# BD0005_1_main.net
KiCad netlist of a schematic drawn in EAGLE
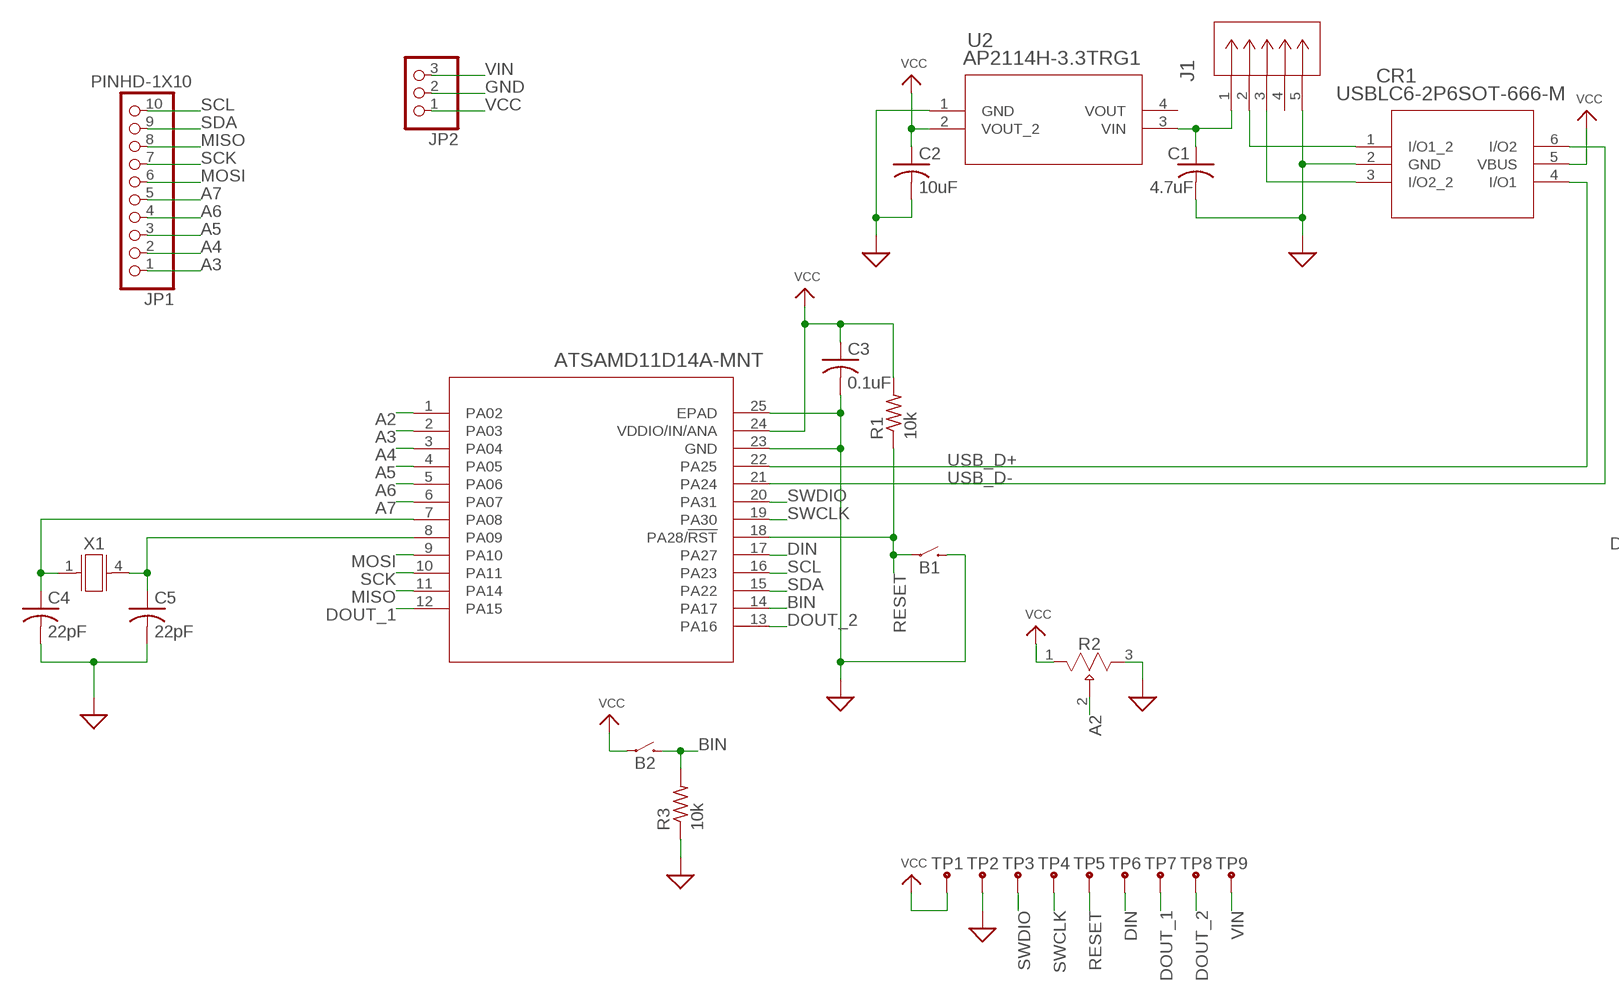
[diagram p0: schematic, sheet 1, part 1 of 2]
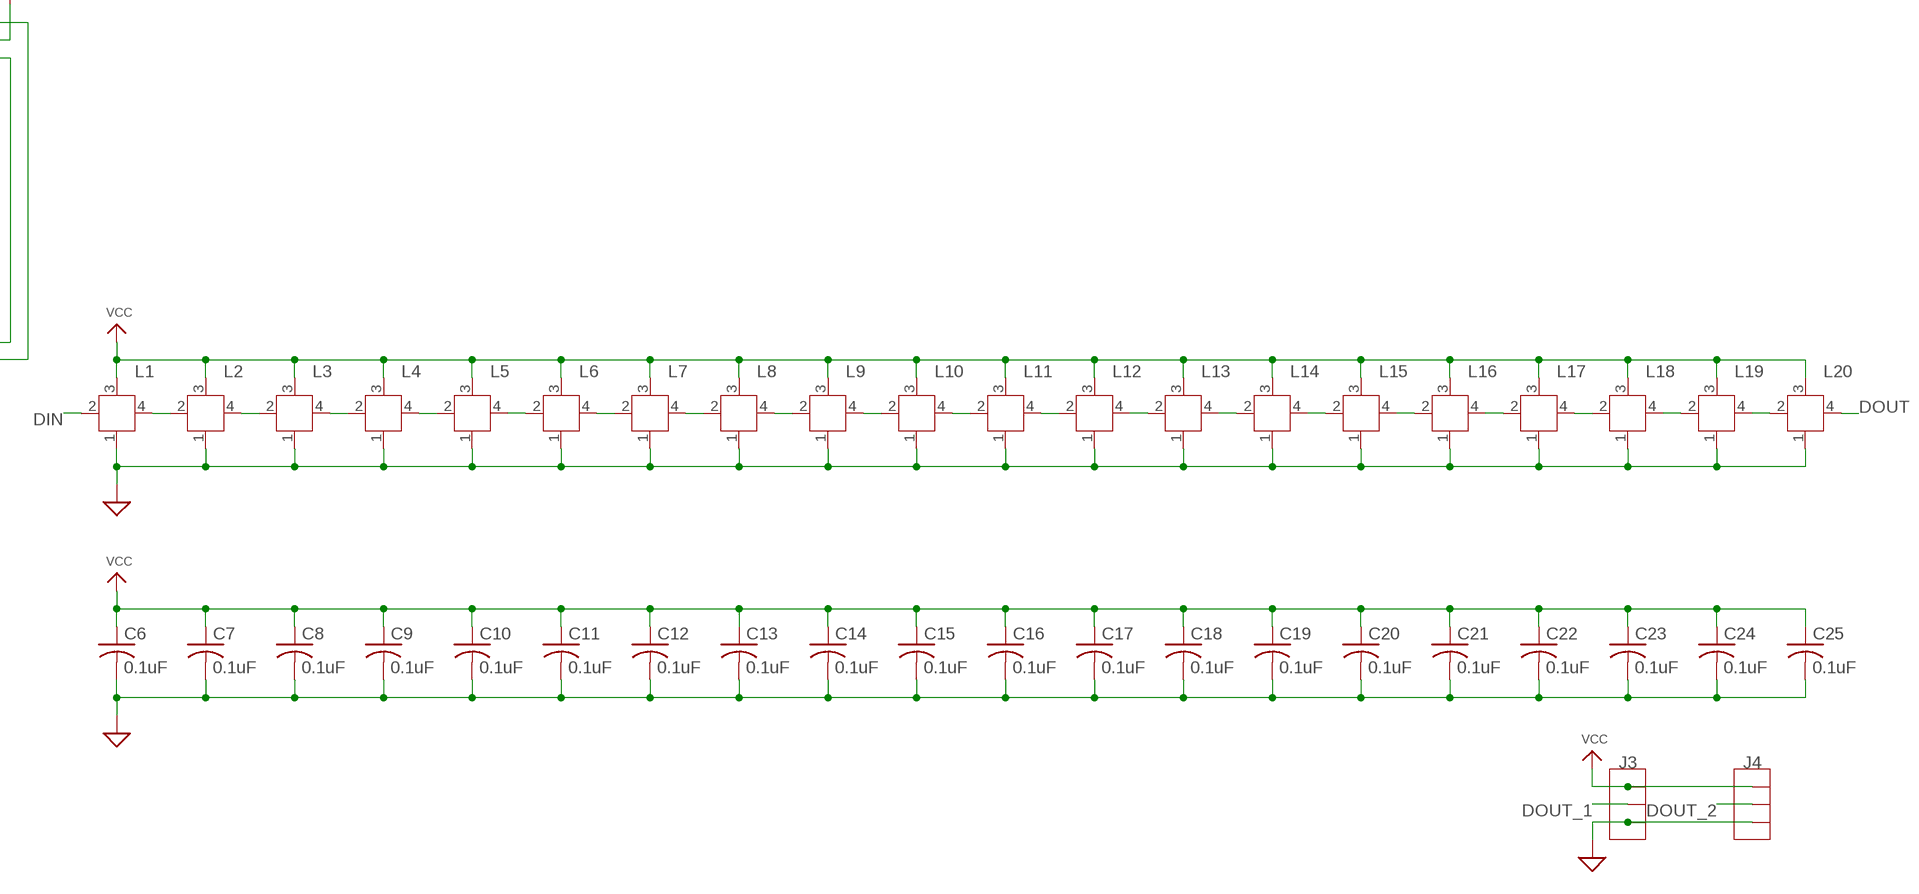
[diagram p1: schematic, sheet 1, part 2 of 2]

(export (version "E")
  (design (tool "Eeschema 10.0.6"))
  (components
    (comp (ref "B1")
      (value "EVQ-P7A01P")
      (footprint "eagle-import:4-SMD_BUTTON")
      (libsource (lib "eagle-import") (part "EVQ-P7A01P"))
    )
    (comp (ref "B2")
      (value "EVQ-P7A01P")
      (footprint "eagle-import:4-SMD_BUTTON")
      (libsource (lib "eagle-import") (part "EVQ-P7A01P"))
    )
    (comp (ref "C1")
      (value "4.7uF")
      (footprint "eagle-import:C0805")
      (libsource (lib "eagle-import") (part "C-USC0805"))
    )
    (comp (ref "C2")
      (value "10uF")
      (footprint "eagle-import:C0805")
      (libsource (lib "eagle-import") (part "C-USC0805"))
    )
    (comp (ref "C3")
      (value "0.1uF")
      (footprint "eagle-import:C0402")
      (libsource (lib "eagle-import") (part "C-USC0402"))
    )
    (comp (ref "C4")
      (value "22pF")
      (footprint "eagle-import:C0402")
      (libsource (lib "eagle-import") (part "C-USC0402"))
    )
    (comp (ref "C5")
      (value "22pF")
      (footprint "eagle-import:C0402")
      (libsource (lib "eagle-import") (part "C-USC0402"))
    )
    (comp (ref "C6")
      (value "0.1uF")
      (footprint "eagle-import:C0402")
      (libsource (lib "eagle-import") (part "C-USC0402"))
    )
    (comp (ref "C7")
      (value "0.1uF")
      (footprint "eagle-import:C0402")
      (libsource (lib "eagle-import") (part "C-USC0402"))
    )
    (comp (ref "C8")
      (value "0.1uF")
      (footprint "eagle-import:C0402")
      (libsource (lib "eagle-import") (part "C-USC0402"))
    )
    (comp (ref "C9")
      (value "0.1uF")
      (footprint "eagle-import:C0402")
      (libsource (lib "eagle-import") (part "C-USC0402"))
    )
    (comp (ref "C10")
      (value "0.1uF")
      (footprint "eagle-import:C0402")
      (libsource (lib "eagle-import") (part "C-USC0402"))
    )
    (comp (ref "C11")
      (value "0.1uF")
      (footprint "eagle-import:C0402")
      (libsource (lib "eagle-import") (part "C-USC0402"))
    )
    (comp (ref "C12")
      (value "0.1uF")
      (footprint "eagle-import:C0402")
      (libsource (lib "eagle-import") (part "C-USC0402"))
    )
    (comp (ref "C13")
      (value "0.1uF")
      (footprint "eagle-import:C0402")
      (libsource (lib "eagle-import") (part "C-USC0402"))
    )
    (comp (ref "C14")
      (value "0.1uF")
      (footprint "eagle-import:C0402")
      (libsource (lib "eagle-import") (part "C-USC0402"))
    )
    (comp (ref "C15")
      (value "0.1uF")
      (footprint "eagle-import:C0402")
      (libsource (lib "eagle-import") (part "C-USC0402"))
    )
    (comp (ref "C16")
      (value "0.1uF")
      (footprint "eagle-import:C0402")
      (libsource (lib "eagle-import") (part "C-USC0402"))
    )
    (comp (ref "C17")
      (value "0.1uF")
      (footprint "eagle-import:C0402")
      (libsource (lib "eagle-import") (part "C-USC0402"))
    )
    (comp (ref "C18")
      (value "0.1uF")
      (footprint "eagle-import:C0402")
      (libsource (lib "eagle-import") (part "C-USC0402"))
    )
    (comp (ref "C19")
      (value "0.1uF")
      (footprint "eagle-import:C0402")
      (libsource (lib "eagle-import") (part "C-USC0402"))
    )
    (comp (ref "C20")
      (value "0.1uF")
      (footprint "eagle-import:C0402")
      (libsource (lib "eagle-import") (part "C-USC0402"))
    )
    (comp (ref "C21")
      (value "0.1uF")
      (footprint "eagle-import:C0402")
      (libsource (lib "eagle-import") (part "C-USC0402"))
    )
    (comp (ref "C22")
      (value "0.1uF")
      (footprint "eagle-import:C0402")
      (libsource (lib "eagle-import") (part "C-USC0402"))
    )
    (comp (ref "C23")
      (value "0.1uF")
      (footprint "eagle-import:C0402")
      (libsource (lib "eagle-import") (part "C-USC0402"))
    )
    (comp (ref "C24")
      (value "0.1uF")
      (footprint "eagle-import:C0402")
      (libsource (lib "eagle-import") (part "C-USC0402"))
    )
    (comp (ref "C25")
      (value "0.1uF")
      (footprint "eagle-import:C0402")
      (libsource (lib "eagle-import") (part "C-USC0402"))
    )
    (comp (ref "CR1")
      (value "USBLC6-2P6SOT-666-M")
      (footprint "eagle-import:SOT-666-M")
      (fields (field (name "MANUFACTURER_PART_NUMBER") "USBLC6-2P6"))
      (libsource (lib "eagle-import") (part "USBLC6-2P6SOT-666-M"))
    )
    (comp (ref "J1")
      (value "1050171001")
      (footprint "eagle-import:CON00679_5")
      (fields (field (name "COPYRIGHT") "Copyright (C) 2016 Accelerated Designs. All rights reserved"))
      (libsource (lib "eagle-import") (part "1050171001"))
    )
    (comp (ref "J3")
      (value "HEADER_1X3FEMALE")
      (footprint "eagle-import:F3SMD")
      (libsource (lib "eagle-import") (part "HEADER_1X3FEMALE"))
    )
    (comp (ref "J4")
      (value "HEADER_1X3FEMALE")
      (footprint "eagle-import:F3SMD")
      (libsource (lib "eagle-import") (part "HEADER_1X3FEMALE"))
    )
    (comp (ref "JP1")
      (value "PINHD-1X10")
      (footprint "eagle-import:1X10-BIG")
      (libsource (lib "eagle-import") (part "PINHD-1X10"))
    )
    (comp (ref "JP2")
      (value "PINHD-1X3")
      (footprint "eagle-import:1X03")
      (libsource (lib "eagle-import") (part "PINHD-1X3"))
    )
    (comp (ref "L1")
      (value "WS2812B")
      (footprint "eagle-import:SK6812")
      (libsource (lib "eagle-import") (part "WS2812B"))
    )
    (comp (ref "L2")
      (value "WS2812B")
      (footprint "eagle-import:SK6812")
      (libsource (lib "eagle-import") (part "WS2812B"))
    )
    (comp (ref "L3")
      (value "WS2812B")
      (footprint "eagle-import:SK6812")
      (libsource (lib "eagle-import") (part "WS2812B"))
    )
    (comp (ref "L4")
      (value "WS2812B")
      (footprint "eagle-import:SK6812")
      (libsource (lib "eagle-import") (part "WS2812B"))
    )
    (comp (ref "L5")
      (value "WS2812B")
      (footprint "eagle-import:SK6812")
      (libsource (lib "eagle-import") (part "WS2812B"))
    )
    (comp (ref "L6")
      (value "WS2812B")
      (footprint "eagle-import:SK6812")
      (libsource (lib "eagle-import") (part "WS2812B"))
    )
    (comp (ref "L7")
      (value "WS2812B")
      (footprint "eagle-import:SK6812")
      (libsource (lib "eagle-import") (part "WS2812B"))
    )
    (comp (ref "L8")
      (value "WS2812B")
      (footprint "eagle-import:SK6812")
      (libsource (lib "eagle-import") (part "WS2812B"))
    )
    (comp (ref "L9")
      (value "WS2812B")
      (footprint "eagle-import:SK6812")
      (libsource (lib "eagle-import") (part "WS2812B"))
    )
    (comp (ref "L10")
      (value "WS2812B")
      (footprint "eagle-import:SK6812")
      (libsource (lib "eagle-import") (part "WS2812B"))
    )
    (comp (ref "L11")
      (value "WS2812B")
      (footprint "eagle-import:SK6812")
      (libsource (lib "eagle-import") (part "WS2812B"))
    )
    (comp (ref "L12")
      (value "WS2812B")
      (footprint "eagle-import:SK6812")
      (libsource (lib "eagle-import") (part "WS2812B"))
    )
    (comp (ref "L13")
      (value "WS2812B")
      (footprint "eagle-import:SK6812")
      (libsource (lib "eagle-import") (part "WS2812B"))
    )
    (comp (ref "L14")
      (value "WS2812B")
      (footprint "eagle-import:SK6812")
      (libsource (lib "eagle-import") (part "WS2812B"))
    )
    (comp (ref "L15")
      (value "WS2812B")
      (footprint "eagle-import:SK6812")
      (libsource (lib "eagle-import") (part "WS2812B"))
    )
    (comp (ref "L16")
      (value "WS2812B")
      (footprint "eagle-import:SK6812")
      (libsource (lib "eagle-import") (part "WS2812B"))
    )
    (comp (ref "L17")
      (value "WS2812B")
      (footprint "eagle-import:SK6812")
      (libsource (lib "eagle-import") (part "WS2812B"))
    )
    (comp (ref "L18")
      (value "WS2812B")
      (footprint "eagle-import:SK6812")
      (libsource (lib "eagle-import") (part "WS2812B"))
    )
    (comp (ref "L19")
      (value "WS2812B")
      (footprint "eagle-import:SK6812")
      (libsource (lib "eagle-import") (part "WS2812B"))
    )
    (comp (ref "L20")
      (value "WS2812B")
      (footprint "eagle-import:SK6812")
      (libsource (lib "eagle-import") (part "WS2812B"))
    )
    (comp (ref "R1")
      (value "10k")
      (footprint "eagle-import:R0402")
      (libsource (lib "eagle-import") (part "R-US_R0402"))
    )
    (comp (ref "R2")
      (value "3352T-1-104LF")
      (footprint "eagle-import:THUMBWHEEL")
      (libsource (lib "eagle-import") (part "3352T-1-104LF"))
    )
    (comp (ref "R3")
      (value "10k")
      (footprint "eagle-import:R0402")
      (libsource (lib "eagle-import") (part "R-US_R0402"))
    )
    (comp (ref "TP1")
      (value "VCC")
      (footprint "eagle-import:TEST_POINT")
      (libsource (lib "eagle-import") (part "TEST_POINT"))
    )
    (comp (ref "TP2")
      (value "GND")
      (footprint "eagle-import:TEST_POINT")
      (libsource (lib "eagle-import") (part "TEST_POINT"))
    )
    (comp (ref "TP3")
      (value "DIO")
      (footprint "eagle-import:TEST_POINT")
      (libsource (lib "eagle-import") (part "TEST_POINT"))
    )
    (comp (ref "TP4")
      (value "CLK")
      (footprint "eagle-import:TEST_POINT")
      (libsource (lib "eagle-import") (part "TEST_POINT"))
    )
    (comp (ref "TP5")
      (value "RST")
      (footprint "eagle-import:TEST_POINT")
      (libsource (lib "eagle-import") (part "TEST_POINT"))
    )
    (comp (ref "TP6")
      (value "DIN")
      (footprint "eagle-import:TEST_POINT")
      (libsource (lib "eagle-import") (part "TEST_POINT"))
    )
    (comp (ref "TP7")
      (value "DO1")
      (footprint "eagle-import:TEST_POINT")
      (libsource (lib "eagle-import") (part "TEST_POINT"))
    )
    (comp (ref "TP8")
      (value "DO2")
      (footprint "eagle-import:TEST_POINT")
      (libsource (lib "eagle-import") (part "TEST_POINT"))
    )
    (comp (ref "TP9")
      (value "VIN")
      (footprint "eagle-import:TEST_POINT")
      (libsource (lib "eagle-import") (part "TEST_POINT"))
    )
    (comp (ref "U1")
      (value "ATSAMD11D14A-MNT")
      (footprint "eagle-import:QFN24_4X4MC")
      (fields (field (name "COPYRIGHT") "Copyright (C) 2018 Accelerated Designs. All rights reserved"))
      (libsource (lib "eagle-import") (part "ATSAMD11D14A-MNT"))
    )
    (comp (ref "U2")
      (value "AP2114H-3.3TRG1")
      (footprint "eagle-import:SOT-223")
      (libsource (lib "eagle-import") (part "AP2114H-3.3TRG1"))
    )
    (comp (ref "X1")
      (value "MC-146-32.7680JKA-A0:ROHS")
      (footprint "eagle-import:4-SMD_FLAT_LEADS")
      (libsource (lib "eagle-import") (part "MC-146-32.7680JKA-A0{colon}ROHS"))
    )
  )
  (nets
    (net (code "1") (name "/A2") (class "Default")
      (node (ref "R2") (pin "2") (pinfunction "P$2_2") (pintype "bidirectional"))
      (node (ref "U1") (pin "1") (pinfunction "PA02_1") (pintype "bidirectional"))
    )
    (net (code "2") (name "/A3") (class "Default")
      (node (ref "JP1") (pin "1") (pinfunction "1_1") (pintype "passive"))
      (node (ref "U1") (pin "2") (pinfunction "PA03_2") (pintype "bidirectional"))
    )
    (net (code "3") (name "/A4") (class "Default")
      (node (ref "JP1") (pin "2") (pinfunction "2_2") (pintype "passive"))
      (node (ref "U1") (pin "3") (pinfunction "PA04_3") (pintype "bidirectional"))
    )
    (net (code "4") (name "/A5") (class "Default")
      (node (ref "JP1") (pin "3") (pinfunction "3_3") (pintype "passive"))
      (node (ref "U1") (pin "4") (pinfunction "PA05_4") (pintype "bidirectional"))
    )
    (net (code "5") (name "/A6") (class "Default")
      (node (ref "JP1") (pin "4") (pinfunction "4_4") (pintype "passive"))
      (node (ref "U1") (pin "5") (pinfunction "PA06_5") (pintype "bidirectional"))
    )
    (net (code "6") (name "/A7") (class "Default")
      (node (ref "JP1") (pin "5") (pinfunction "5_5") (pintype "passive"))
      (node (ref "U1") (pin "6") (pinfunction "PA07_6") (pintype "bidirectional"))
    )
    (net (code "7") (name "/BIN") (class "Default")
      (node (ref "B2") (pin "2A") (pinfunction "P$2_2A") (pintype "bidirectional"))
      (node (ref "B2") (pin "2B") (pinfunction "P$2_2B") (pintype "bidirectional"))
      (node (ref "R3") (pin "2") (pinfunction "2_2") (pintype "passive"))
      (node (ref "U1") (pin "14") (pinfunction "PA17_14") (pintype "bidirectional"))
    )
    (net (code "8") (name "/DIN") (class "Default")
      (node (ref "L1") (pin "2") (pinfunction "DIN_2") (pintype "bidirectional"))
      (node (ref "TP6") (pin "P$1") (pinfunction "P$1_P$1") (pintype "input"))
      (node (ref "U1") (pin "17") (pinfunction "PA27_17") (pintype "bidirectional"))
    )
    (net (code "9") (name "/DOUT") (class "Default")
      (node (ref "L20") (pin "4") (pinfunction "DOUT_4") (pintype "bidirectional"))
    )
    (net (code "10") (name "/DOUT_1") (class "Default")
      (node (ref "J3") (pin "2A") (pinfunction "P$2_2A") (pintype "bidirectional"))
      (node (ref "J3") (pin "2B") (pinfunction "P$2_2B") (pintype "bidirectional"))
      (node (ref "TP7") (pin "P$1") (pinfunction "P$1_P$1") (pintype "input"))
      (node (ref "U1") (pin "12") (pinfunction "PA15_12") (pintype "bidirectional"))
    )
    (net (code "11") (name "/DOUT_2") (class "Default")
      (node (ref "J4") (pin "2A") (pinfunction "P$2_2A") (pintype "bidirectional"))
      (node (ref "J4") (pin "2B") (pinfunction "P$2_2B") (pintype "bidirectional"))
      (node (ref "TP8") (pin "P$1") (pinfunction "P$1_P$1") (pintype "input"))
      (node (ref "U1") (pin "13") (pinfunction "PA16_13") (pintype "bidirectional"))
    )
    (net (code "12") (name "/MISO") (class "Default")
      (node (ref "JP1") (pin "8") (pinfunction "8_8") (pintype "passive"))
      (node (ref "U1") (pin "11") (pinfunction "PA14_11") (pintype "bidirectional"))
    )
    (net (code "13") (name "/MOSI") (class "Default")
      (node (ref "JP1") (pin "6") (pinfunction "6_6") (pintype "passive"))
      (node (ref "U1") (pin "9") (pinfunction "PA10_9") (pintype "bidirectional"))
    )
    (net (code "14") (name "/RESET") (class "Default")
      (node (ref "B1") (pin "1A") (pinfunction "P$1_1A") (pintype "bidirectional"))
      (node (ref "B1") (pin "1B") (pinfunction "P$1_1B") (pintype "bidirectional"))
      (node (ref "R1") (pin "1") (pinfunction "1_1") (pintype "passive"))
      (node (ref "TP5") (pin "P$1") (pinfunction "P$1_P$1") (pintype "input"))
      (node (ref "U1") (pin "18") (pinfunction "PA28/~{RST}_18") (pintype "bidirectional"))
    )
    (net (code "15") (name "/SCK") (class "Default")
      (node (ref "JP1") (pin "7") (pinfunction "7_7") (pintype "passive"))
      (node (ref "U1") (pin "10") (pinfunction "PA11_10") (pintype "bidirectional"))
    )
    (net (code "16") (name "/SCL") (class "Default")
      (node (ref "JP1") (pin "10") (pinfunction "10_10") (pintype "passive"))
      (node (ref "U1") (pin "16") (pinfunction "PA23_16") (pintype "bidirectional"))
    )
    (net (code "17") (name "/SDA") (class "Default")
      (node (ref "JP1") (pin "9") (pinfunction "9_9") (pintype "passive"))
      (node (ref "U1") (pin "15") (pinfunction "PA22_15") (pintype "bidirectional"))
    )
    (net (code "18") (name "/SWCLK") (class "Default")
      (node (ref "TP4") (pin "P$1") (pinfunction "P$1_P$1") (pintype "input"))
      (node (ref "U1") (pin "19") (pinfunction "PA30_19") (pintype "bidirectional"))
    )
    (net (code "19") (name "/SWDIO") (class "Default")
      (node (ref "TP3") (pin "P$1") (pinfunction "P$1_P$1") (pintype "input"))
      (node (ref "U1") (pin "20") (pinfunction "PA31_20") (pintype "bidirectional"))
    )
    (net (code "20") (name "/USB_D+") (class "Default")
      (node (ref "CR1") (pin "4") (pinfunction "I/O1_4") (pintype "bidirectional"))
      (node (ref "U1") (pin "22") (pinfunction "PA25_22") (pintype "bidirectional"))
    )
    (net (code "21") (name "/USB_D-") (class "Default")
      (node (ref "CR1") (pin "6") (pinfunction "I/O2_6") (pintype "bidirectional"))
      (node (ref "U1") (pin "21") (pinfunction "PA24_21") (pintype "bidirectional"))
    )
    (net (code "22") (name "/VIN") (class "Default")
      (node (ref "C1") (pin "1") (pinfunction "1_1") (pintype "passive"))
      (node (ref "J1") (pin "1") (pinfunction "1_1") (pintype "passive"))
      (node (ref "JP2") (pin "3") (pinfunction "3_3") (pintype "passive"))
      (node (ref "TP9") (pin "P$1") (pinfunction "P$1_P$1") (pintype "input"))
      (node (ref "U2") (pin "3") (pinfunction "VIN_3") (pintype "input"))
    )
    (net (code "23") (name "Net-(CR1-I{slash}O1_2)") (class "Default")
      (node (ref "CR1") (pin "1") (pinfunction "I/O1_2_1") (pintype "bidirectional"))
      (node (ref "J1") (pin "2") (pinfunction "2_2") (pintype "passive"))
    )
    (net (code "24") (name "Net-(CR1-I{slash}O2_2)") (class "Default")
      (node (ref "CR1") (pin "3") (pinfunction "I/O2_2_3") (pintype "bidirectional"))
      (node (ref "J1") (pin "3") (pinfunction "3_3") (pintype "passive"))
    )
    (net (code "25") (name "Net-(L1-DOUT)") (class "Default")
      (node (ref "L1") (pin "4") (pinfunction "DOUT_4") (pintype "bidirectional"))
      (node (ref "L2") (pin "2") (pinfunction "DIN_2") (pintype "bidirectional"))
    )
    (net (code "26") (name "Net-(L2-DOUT)") (class "Default")
      (node (ref "L2") (pin "4") (pinfunction "DOUT_4") (pintype "bidirectional"))
      (node (ref "L3") (pin "2") (pinfunction "DIN_2") (pintype "bidirectional"))
    )
    (net (code "27") (name "Net-(L3-DOUT)") (class "Default")
      (node (ref "L3") (pin "4") (pinfunction "DOUT_4") (pintype "bidirectional"))
      (node (ref "L4") (pin "2") (pinfunction "DIN_2") (pintype "bidirectional"))
    )
    (net (code "28") (name "Net-(L4-DOUT)") (class "Default")
      (node (ref "L4") (pin "4") (pinfunction "DOUT_4") (pintype "bidirectional"))
      (node (ref "L5") (pin "2") (pinfunction "DIN_2") (pintype "bidirectional"))
    )
    (net (code "29") (name "Net-(L5-DOUT)") (class "Default")
      (node (ref "L5") (pin "4") (pinfunction "DOUT_4") (pintype "bidirectional"))
      (node (ref "L6") (pin "2") (pinfunction "DIN_2") (pintype "bidirectional"))
    )
    (net (code "30") (name "Net-(L6-DOUT)") (class "Default")
      (node (ref "L6") (pin "4") (pinfunction "DOUT_4") (pintype "bidirectional"))
      (node (ref "L7") (pin "2") (pinfunction "DIN_2") (pintype "bidirectional"))
    )
    (net (code "31") (name "Net-(L7-DOUT)") (class "Default")
      (node (ref "L7") (pin "4") (pinfunction "DOUT_4") (pintype "bidirectional"))
      (node (ref "L8") (pin "2") (pinfunction "DIN_2") (pintype "bidirectional"))
    )
    (net (code "32") (name "Net-(L8-DOUT)") (class "Default")
      (node (ref "L8") (pin "4") (pinfunction "DOUT_4") (pintype "bidirectional"))
      (node (ref "L9") (pin "2") (pinfunction "DIN_2") (pintype "bidirectional"))
    )
    (net (code "33") (name "Net-(L10-DIN)") (class "Default")
      (node (ref "L10") (pin "2") (pinfunction "DIN_2") (pintype "bidirectional"))
      (node (ref "L9") (pin "4") (pinfunction "DOUT_4") (pintype "bidirectional"))
    )
    (net (code "34") (name "Net-(L10-DOUT)") (class "Default")
      (node (ref "L10") (pin "4") (pinfunction "DOUT_4") (pintype "bidirectional"))
      (node (ref "L11") (pin "2") (pinfunction "DIN_2") (pintype "bidirectional"))
    )
    (net (code "35") (name "Net-(L11-DOUT)") (class "Default")
      (node (ref "L11") (pin "4") (pinfunction "DOUT_4") (pintype "bidirectional"))
      (node (ref "L12") (pin "2") (pinfunction "DIN_2") (pintype "bidirectional"))
    )
    (net (code "36") (name "Net-(L12-DOUT)") (class "Default")
      (node (ref "L12") (pin "4") (pinfunction "DOUT_4") (pintype "bidirectional"))
      (node (ref "L13") (pin "2") (pinfunction "DIN_2") (pintype "bidirectional"))
    )
    (net (code "37") (name "Net-(L13-DOUT)") (class "Default")
      (node (ref "L13") (pin "4") (pinfunction "DOUT_4") (pintype "bidirectional"))
      (node (ref "L14") (pin "2") (pinfunction "DIN_2") (pintype "bidirectional"))
    )
    (net (code "38") (name "Net-(L14-DOUT)") (class "Default")
      (node (ref "L14") (pin "4") (pinfunction "DOUT_4") (pintype "bidirectional"))
      (node (ref "L15") (pin "2") (pinfunction "DIN_2") (pintype "bidirectional"))
    )
    (net (code "39") (name "Net-(L15-DOUT)") (class "Default")
      (node (ref "L15") (pin "4") (pinfunction "DOUT_4") (pintype "bidirectional"))
      (node (ref "L16") (pin "2") (pinfunction "DIN_2") (pintype "bidirectional"))
    )
    (net (code "40") (name "Net-(L16-DOUT)") (class "Default")
      (node (ref "L16") (pin "4") (pinfunction "DOUT_4") (pintype "bidirectional"))
      (node (ref "L17") (pin "2") (pinfunction "DIN_2") (pintype "bidirectional"))
    )
    (net (code "41") (name "Net-(L17-DOUT)") (class "Default")
      (node (ref "L17") (pin "4") (pinfunction "DOUT_4") (pintype "bidirectional"))
      (node (ref "L18") (pin "2") (pinfunction "DIN_2") (pintype "bidirectional"))
    )
    (net (code "42") (name "Net-(L18-DOUT)") (class "Default")
      (node (ref "L18") (pin "4") (pinfunction "DOUT_4") (pintype "bidirectional"))
      (node (ref "L19") (pin "2") (pinfunction "DIN_2") (pintype "bidirectional"))
    )
    (net (code "43") (name "Net-(L19-DOUT)") (class "Default")
      (node (ref "L19") (pin "4") (pinfunction "DOUT_4") (pintype "bidirectional"))
      (node (ref "L20") (pin "2") (pinfunction "DIN_2") (pintype "bidirectional"))
    )
    (net (code "44") (name "Net-(U1-PA08)") (class "Default")
      (node (ref "C4") (pin "1") (pinfunction "1_1") (pintype "passive"))
      (node (ref "U1") (pin "7") (pinfunction "PA08_7") (pintype "bidirectional"))
      (node (ref "X1") (pin "1") (pinfunction "P$1_1") (pintype "bidirectional"))
    )
    (net (code "45") (name "Net-(U1-PA09)") (class "Default")
      (node (ref "C5") (pin "1") (pinfunction "1_1") (pintype "passive"))
      (node (ref "U1") (pin "8") (pinfunction "PA09_8") (pintype "bidirectional"))
      (node (ref "X1") (pin "4") (pinfunction "P$2_4") (pintype "bidirectional"))
    )
    (net (code "46") (name "SUP") (class "Default")
      (node (ref "B1") (pin "2A") (pinfunction "P$2_2A") (pintype "bidirectional"))
      (node (ref "B1") (pin "2B") (pinfunction "P$2_2B") (pintype "bidirectional"))
      (node (ref "C1") (pin "2") (pinfunction "2_2") (pintype "passive"))
      (node (ref "C10") (pin "2") (pinfunction "2_2") (pintype "passive"))
      (node (ref "C11") (pin "2") (pinfunction "2_2") (pintype "passive"))
      (node (ref "C12") (pin "2") (pinfunction "2_2") (pintype "passive"))
      (node (ref "C13") (pin "2") (pinfunction "2_2") (pintype "passive"))
      (node (ref "C14") (pin "2") (pinfunction "2_2") (pintype "passive"))
      (node (ref "C15") (pin "2") (pinfunction "2_2") (pintype "passive"))
      (node (ref "C16") (pin "2") (pinfunction "2_2") (pintype "passive"))
      (node (ref "C17") (pin "2") (pinfunction "2_2") (pintype "passive"))
      (node (ref "C18") (pin "2") (pinfunction "2_2") (pintype "passive"))
      (node (ref "C19") (pin "2") (pinfunction "2_2") (pintype "passive"))
      (node (ref "C2") (pin "2") (pinfunction "2_2") (pintype "passive"))
      (node (ref "C20") (pin "2") (pinfunction "2_2") (pintype "passive"))
      (node (ref "C21") (pin "2") (pinfunction "2_2") (pintype "passive"))
      (node (ref "C22") (pin "2") (pinfunction "2_2") (pintype "passive"))
      (node (ref "C23") (pin "2") (pinfunction "2_2") (pintype "passive"))
      (node (ref "C24") (pin "2") (pinfunction "2_2") (pintype "passive"))
      (node (ref "C25") (pin "2") (pinfunction "2_2") (pintype "passive"))
      (node (ref "C3") (pin "2") (pinfunction "2_2") (pintype "passive"))
      (node (ref "C4") (pin "2") (pinfunction "2_2") (pintype "passive"))
      (node (ref "C5") (pin "2") (pinfunction "2_2") (pintype "passive"))
      (node (ref "C6") (pin "2") (pinfunction "2_2") (pintype "passive"))
      (node (ref "C7") (pin "2") (pinfunction "2_2") (pintype "passive"))
      (node (ref "C8") (pin "2") (pinfunction "2_2") (pintype "passive"))
      (node (ref "C9") (pin "2") (pinfunction "2_2") (pintype "passive"))
      (node (ref "CR1") (pin "2") (pinfunction "GND_2") (pintype "power_in"))
      (node (ref "J1") (pin "5") (pinfunction "5_5") (pintype "passive"))
      (node (ref "J3") (pin "3A") (pinfunction "P$3_3A") (pintype "bidirectional"))
      (node (ref "J3") (pin "3B") (pinfunction "P$3_3B") (pintype "bidirectional"))
      (node (ref "J4") (pin "3A") (pinfunction "P$3_3A") (pintype "bidirectional"))
      (node (ref "J4") (pin "3B") (pinfunction "P$3_3B") (pintype "bidirectional"))
      (node (ref "JP2") (pin "2") (pinfunction "2_2") (pintype "passive"))
      (node (ref "L1") (pin "1") (pinfunction "VSS_1") (pintype "bidirectional"))
      (node (ref "L10") (pin "1") (pinfunction "VSS_1") (pintype "bidirectional"))
      (node (ref "L11") (pin "1") (pinfunction "VSS_1") (pintype "bidirectional"))
      (node (ref "L12") (pin "1") (pinfunction "VSS_1") (pintype "bidirectional"))
      (node (ref "L13") (pin "1") (pinfunction "VSS_1") (pintype "bidirectional"))
      (node (ref "L14") (pin "1") (pinfunction "VSS_1") (pintype "bidirectional"))
      (node (ref "L15") (pin "1") (pinfunction "VSS_1") (pintype "bidirectional"))
      (node (ref "L16") (pin "1") (pinfunction "VSS_1") (pintype "bidirectional"))
      (node (ref "L17") (pin "1") (pinfunction "VSS_1") (pintype "bidirectional"))
      (node (ref "L18") (pin "1") (pinfunction "VSS_1") (pintype "bidirectional"))
      (node (ref "L19") (pin "1") (pinfunction "VSS_1") (pintype "bidirectional"))
      (node (ref "L2") (pin "1") (pinfunction "VSS_1") (pintype "bidirectional"))
      (node (ref "L20") (pin "1") (pinfunction "VSS_1") (pintype "bidirectional"))
      (node (ref "L3") (pin "1") (pinfunction "VSS_1") (pintype "bidirectional"))
      (node (ref "L4") (pin "1") (pinfunction "VSS_1") (pintype "bidirectional"))
      (node (ref "L5") (pin "1") (pinfunction "VSS_1") (pintype "bidirectional"))
      (node (ref "L6") (pin "1") (pinfunction "VSS_1") (pintype "bidirectional"))
      (node (ref "L7") (pin "1") (pinfunction "VSS_1") (pintype "bidirectional"))
      (node (ref "L8") (pin "1") (pinfunction "VSS_1") (pintype "bidirectional"))
      (node (ref "L9") (pin "1") (pinfunction "VSS_1") (pintype "bidirectional"))
      (node (ref "R2") (pin "3") (pinfunction "P$3_3") (pintype "bidirectional"))
      (node (ref "R3") (pin "1") (pinfunction "1_1") (pintype "passive"))
      (node (ref "TP2") (pin "P$1") (pinfunction "P$1_P$1") (pintype "input"))
      (node (ref "U1") (pin "23") (pinfunction "GND_23") (pintype "passive"))
      (node (ref "U1") (pin "25") (pinfunction "EPAD_25") (pintype "passive"))
      (node (ref "U2") (pin "1") (pinfunction "GND_1") (pintype "passive"))
    )
    (net (code "47") (name "VCC") (class "Default")
      (node (ref "B2") (pin "1A") (pinfunction "P$1_1A") (pintype "bidirectional"))
      (node (ref "B2") (pin "1B") (pinfunction "P$1_1B") (pintype "bidirectional"))
      (node (ref "C10") (pin "1") (pinfunction "1_1") (pintype "passive"))
      (node (ref "C11") (pin "1") (pinfunction "1_1") (pintype "passive"))
      (node (ref "C12") (pin "1") (pinfunction "1_1") (pintype "passive"))
      (node (ref "C13") (pin "1") (pinfunction "1_1") (pintype "passive"))
      (node (ref "C14") (pin "1") (pinfunction "1_1") (pintype "passive"))
      (node (ref "C15") (pin "1") (pinfunction "1_1") (pintype "passive"))
      (node (ref "C16") (pin "1") (pinfunction "1_1") (pintype "passive"))
      (node (ref "C17") (pin "1") (pinfunction "1_1") (pintype "passive"))
      (node (ref "C18") (pin "1") (pinfunction "1_1") (pintype "passive"))
      (node (ref "C19") (pin "1") (pinfunction "1_1") (pintype "passive"))
      (node (ref "C2") (pin "1") (pinfunction "1_1") (pintype "passive"))
      (node (ref "C20") (pin "1") (pinfunction "1_1") (pintype "passive"))
      (node (ref "C21") (pin "1") (pinfunction "1_1") (pintype "passive"))
      (node (ref "C22") (pin "1") (pinfunction "1_1") (pintype "passive"))
      (node (ref "C23") (pin "1") (pinfunction "1_1") (pintype "passive"))
      (node (ref "C24") (pin "1") (pinfunction "1_1") (pintype "passive"))
      (node (ref "C25") (pin "1") (pinfunction "1_1") (pintype "passive"))
      (node (ref "C3") (pin "1") (pinfunction "1_1") (pintype "passive"))
      (node (ref "C6") (pin "1") (pinfunction "1_1") (pintype "passive"))
      (node (ref "C7") (pin "1") (pinfunction "1_1") (pintype "passive"))
      (node (ref "C8") (pin "1") (pinfunction "1_1") (pintype "passive"))
      (node (ref "C9") (pin "1") (pinfunction "1_1") (pintype "passive"))
      (node (ref "CR1") (pin "5") (pinfunction "VBUS_5") (pintype "power_in"))
      (node (ref "J3") (pin "1A") (pinfunction "P$1_1A") (pintype "bidirectional"))
      (node (ref "J3") (pin "1B") (pinfunction "P$1_1B") (pintype "bidirectional"))
      (node (ref "J4") (pin "1A") (pinfunction "P$1_1A") (pintype "bidirectional"))
      (node (ref "J4") (pin "1B") (pinfunction "P$1_1B") (pintype "bidirectional"))
      (node (ref "JP2") (pin "1") (pinfunction "1_1") (pintype "passive"))
      (node (ref "L1") (pin "3") (pinfunction "VDD_3") (pintype "bidirectional"))
      (node (ref "L10") (pin "3") (pinfunction "VDD_3") (pintype "bidirectional"))
      (node (ref "L11") (pin "3") (pinfunction "VDD_3") (pintype "bidirectional"))
      (node (ref "L12") (pin "3") (pinfunction "VDD_3") (pintype "bidirectional"))
      (node (ref "L13") (pin "3") (pinfunction "VDD_3") (pintype "bidirectional"))
      (node (ref "L14") (pin "3") (pinfunction "VDD_3") (pintype "bidirectional"))
      (node (ref "L15") (pin "3") (pinfunction "VDD_3") (pintype "bidirectional"))
      (node (ref "L16") (pin "3") (pinfunction "VDD_3") (pintype "bidirectional"))
      (node (ref "L17") (pin "3") (pinfunction "VDD_3") (pintype "bidirectional"))
      (node (ref "L18") (pin "3") (pinfunction "VDD_3") (pintype "bidirectional"))
      (node (ref "L19") (pin "3") (pinfunction "VDD_3") (pintype "bidirectional"))
      (node (ref "L2") (pin "3") (pinfunction "VDD_3") (pintype "bidirectional"))
      (node (ref "L20") (pin "3") (pinfunction "VDD_3") (pintype "bidirectional"))
      (node (ref "L3") (pin "3") (pinfunction "VDD_3") (pintype "bidirectional"))
      (node (ref "L4") (pin "3") (pinfunction "VDD_3") (pintype "bidirectional"))
      (node (ref "L5") (pin "3") (pinfunction "VDD_3") (pintype "bidirectional"))
      (node (ref "L6") (pin "3") (pinfunction "VDD_3") (pintype "bidirectional"))
      (node (ref "L7") (pin "3") (pinfunction "VDD_3") (pintype "bidirectional"))
      (node (ref "L8") (pin "3") (pinfunction "VDD_3") (pintype "bidirectional"))
      (node (ref "L9") (pin "3") (pinfunction "VDD_3") (pintype "bidirectional"))
      (node (ref "R1") (pin "2") (pinfunction "2_2") (pintype "passive"))
      (node (ref "R2") (pin "1") (pinfunction "P$1_1") (pintype "bidirectional"))
      (node (ref "TP1") (pin "P$1") (pinfunction "P$1_P$1") (pintype "input"))
      (node (ref "U1") (pin "24") (pinfunction "VDDIO/IN/ANA_24") (pintype "power_in"))
      (node (ref "U2") (pin "2") (pinfunction "VOUT_2_2") (pintype "output"))
    )
    (net (code "48") (name "unconnected-(J1-Pad4)") (class "Default")
      (node (ref "J1") (pin "4") (pinfunction "4_4") (pintype "passive"))
    )
    (net (code "49") (name "unconnected-(U2-VOUT-Pad4)") (class "Default")
      (node (ref "U2") (pin "4") (pinfunction "VOUT_4") (pintype "output"))
    )
  )
)
